# SS.net
KiCad netlist of a schematic drawn in EAGLE
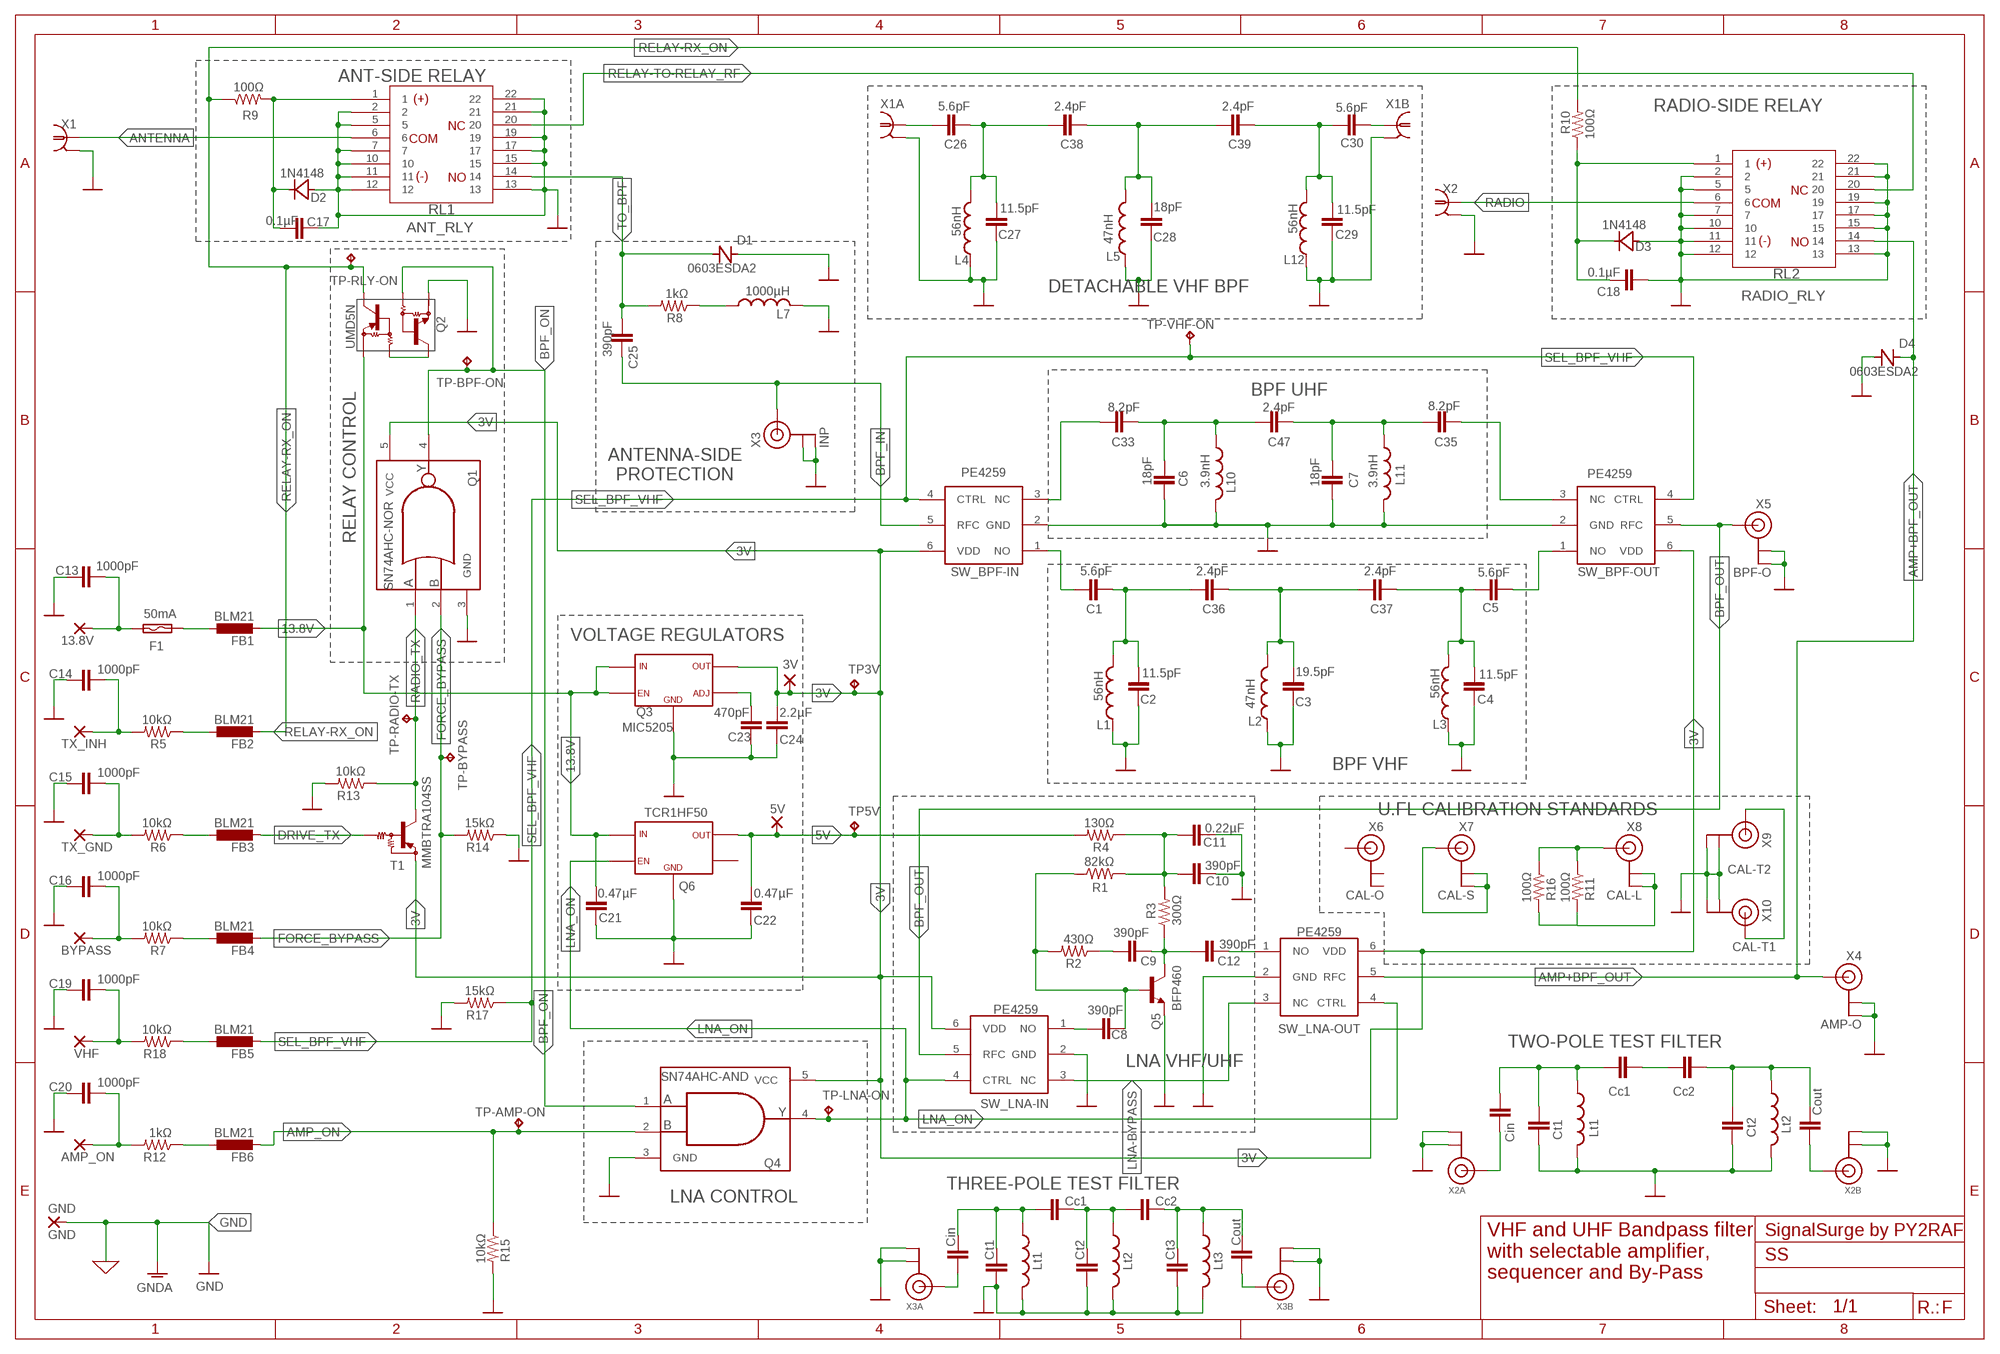
[diagram p0: schematic, sheet 1]

(export (version "E")
  (design (tool "Eeschema 10.0.6"))
  (components
    (comp (ref "3V")
      (value "3V")
      (footprint "eagle-import:JUMPER1")
      (libsource (lib "eagle-import") (part "JUMPER-1"))
    )
    (comp (ref "5V")
      (value "5V")
      (footprint "eagle-import:JUMPER1")
      (libsource (lib "eagle-import") (part "JUMPER-1"))
    )
    (comp (ref "13.8V")
      (value "13.8V")
      (footprint "eagle-import:JUMPER1")
      (fields (field (name "SPICEPREFIX") "X"))
      (libsource (lib "eagle-import") (part "JUMPER-1"))
    )
    (comp (ref "AMP_ON")
      (value "AMP_ON")
      (footprint "eagle-import:JUMPER1")
      (libsource (lib "eagle-import") (part "JUMPER-1"))
    )
    (comp (ref "BYPASS")
      (value "BYPASS")
      (footprint "eagle-import:JUMPER1")
      (libsource (lib "eagle-import") (part "JUMPER-1"))
    )
    (comp (ref "C1")
      (value "5.6pF")
      (footprint "eagle-import:0805")
      (libsource (lib "eagle-import") (part "C-0805"))
    )
    (comp (ref "C2")
      (value "11.5pF")
      (footprint "eagle-import:0805")
      (libsource (lib "eagle-import") (part "C-0805"))
    )
    (comp (ref "C3")
      (value "19.5pF")
      (footprint "eagle-import:0805")
      (libsource (lib "eagle-import") (part "C-0805"))
    )
    (comp (ref "C4")
      (value "11.5pF")
      (footprint "eagle-import:0805")
      (libsource (lib "eagle-import") (part "C-0805"))
    )
    (comp (ref "C5")
      (value "5.6pF")
      (footprint "eagle-import:0805")
      (libsource (lib "eagle-import") (part "C-0805"))
    )
    (comp (ref "C6")
      (value "18pF")
      (footprint "eagle-import:0805")
      (libsource (lib "eagle-import") (part "C-0805"))
    )
    (comp (ref "C7")
      (value "18pF")
      (footprint "eagle-import:0805")
      (libsource (lib "eagle-import") (part "C-0805"))
    )
    (comp (ref "C8")
      (value "390pF")
      (footprint "eagle-import:0805")
      (libsource (lib "eagle-import") (part "C-0805"))
    )
    (comp (ref "C9")
      (value "390pF")
      (footprint "eagle-import:0805")
      (libsource (lib "eagle-import") (part "C-0805"))
    )
    (comp (ref "C10")
      (value "390pF")
      (footprint "eagle-import:0805")
      (libsource (lib "eagle-import") (part "C-0805"))
    )
    (comp (ref "C11")
      (value "0.22µF")
      (footprint "eagle-import:0805")
      (libsource (lib "eagle-import") (part "C-0805"))
    )
    (comp (ref "C12")
      (value "390pF")
      (footprint "eagle-import:0805")
      (libsource (lib "eagle-import") (part "C-0805"))
    )
    (comp (ref "C13")
      (value "1000pF")
      (footprint "eagle-import:0805")
      (libsource (lib "eagle-import") (part "C-0805"))
    )
    (comp (ref "C14")
      (value "1000pF")
      (footprint "eagle-import:0805")
      (libsource (lib "eagle-import") (part "C-0805"))
    )
    (comp (ref "C15")
      (value "1000pF")
      (footprint "eagle-import:0805")
      (libsource (lib "eagle-import") (part "C-0805"))
    )
    (comp (ref "C16")
      (value "1000pF")
      (footprint "eagle-import:0805")
      (libsource (lib "eagle-import") (part "C-0805"))
    )
    (comp (ref "C17")
      (value "0.1µF")
      (footprint "eagle-import:0805")
      (libsource (lib "eagle-import") (part "C-0805"))
    )
    (comp (ref "C18")
      (value "0.1µF")
      (footprint "eagle-import:0805")
      (libsource (lib "eagle-import") (part "C-0805"))
    )
    (comp (ref "C19")
      (value "1000pF")
      (footprint "eagle-import:0805")
      (libsource (lib "eagle-import") (part "C-0805"))
    )
    (comp (ref "C20")
      (value "1000pF")
      (footprint "eagle-import:0805")
      (libsource (lib "eagle-import") (part "C-0805"))
    )
    (comp (ref "C21")
      (value "0.47µF")
      (footprint "eagle-import:0805")
      (libsource (lib "eagle-import") (part "C-0805"))
    )
    (comp (ref "C22")
      (value "0.47µF")
      (footprint "eagle-import:0805")
      (libsource (lib "eagle-import") (part "C-0805"))
    )
    (comp (ref "C23")
      (value "470pF")
      (footprint "eagle-import:0805")
      (libsource (lib "eagle-import") (part "C-0805"))
    )
    (comp (ref "C24")
      (value "2.2µF")
      (footprint "eagle-import:0805")
      (libsource (lib "eagle-import") (part "C-0805"))
    )
    (comp (ref "C25")
      (value "390pF")
      (footprint "eagle-import:0805")
      (libsource (lib "eagle-import") (part "C-0805"))
    )
    (comp (ref "C26")
      (value "5.6pF")
      (footprint "eagle-import:0805")
      (libsource (lib "eagle-import") (part "C-0805"))
    )
    (comp (ref "C27")
      (value "11.5pF")
      (footprint "eagle-import:0805")
      (libsource (lib "eagle-import") (part "C-0805"))
    )
    (comp (ref "C28")
      (value "18pF")
      (footprint "eagle-import:0805")
      (libsource (lib "eagle-import") (part "C-0805"))
    )
    (comp (ref "C29")
      (value "11.5pF")
      (footprint "eagle-import:0805")
      (libsource (lib "eagle-import") (part "C-0805"))
    )
    (comp (ref "C30")
      (value "5.6pF")
      (footprint "eagle-import:0805")
      (libsource (lib "eagle-import") (part "C-0805"))
    )
    (comp (ref "C31")
      (value "Ct1")
      (footprint "eagle-import:0805")
      (libsource (lib "eagle-import") (part "C-0805"))
    )
    (comp (ref "C32")
      (value "Ct2")
      (footprint "eagle-import:0805")
      (libsource (lib "eagle-import") (part "C-0805"))
    )
    (comp (ref "C33")
      (value "8.2pF")
      (footprint "eagle-import:0805")
      (libsource (lib "eagle-import") (part "C-0805"))
    )
    (comp (ref "C35")
      (value "8.2pF")
      (footprint "eagle-import:0805")
      (libsource (lib "eagle-import") (part "C-0805"))
    )
    (comp (ref "C36")
      (value "2.4pF")
      (footprint "eagle-import:0805")
      (libsource (lib "eagle-import") (part "C-0805"))
    )
    (comp (ref "C37")
      (value "2.4pF")
      (footprint "eagle-import:0805")
      (libsource (lib "eagle-import") (part "C-0805"))
    )
    (comp (ref "C38")
      (value "2.4pF")
      (footprint "eagle-import:0805")
      (libsource (lib "eagle-import") (part "C-0805"))
    )
    (comp (ref "C39")
      (value "2.4pF")
      (footprint "eagle-import:0805")
      (libsource (lib "eagle-import") (part "C-0805"))
    )
    (comp (ref "C40")
      (value "Cin")
      (footprint "eagle-import:0805")
      (libsource (lib "eagle-import") (part "C-0805"))
    )
    (comp (ref "C41")
      (value "Ct1")
      (footprint "eagle-import:0805")
      (libsource (lib "eagle-import") (part "C-0805"))
    )
    (comp (ref "C42")
      (value "Cc1")
      (footprint "eagle-import:0805")
      (libsource (lib "eagle-import") (part "C-0805"))
    )
    (comp (ref "C43")
      (value "Ct2")
      (footprint "eagle-import:0805")
      (libsource (lib "eagle-import") (part "C-0805"))
    )
    (comp (ref "C44")
      (value "Cc2")
      (footprint "eagle-import:0805")
      (libsource (lib "eagle-import") (part "C-0805"))
    )
    (comp (ref "C45")
      (value "Ct3")
      (footprint "eagle-import:0805")
      (libsource (lib "eagle-import") (part "C-0805"))
    )
    (comp (ref "C46")
      (value "Cout")
      (footprint "eagle-import:0805")
      (libsource (lib "eagle-import") (part "C-0805"))
    )
    (comp (ref "C47")
      (value "2.4pF")
      (footprint "eagle-import:0805")
      (libsource (lib "eagle-import") (part "C-0805"))
    )
    (comp (ref "D1")
      (value "0603ESDA2")
      (footprint "eagle-import:0603")
      (libsource (lib "eagle-import") (part "0603ESDA2"))
    )
    (comp (ref "D2")
      (value "1N4148")
      (footprint "eagle-import:SOD-323")
      (libsource (lib "eagle-import") (part "D-SOD323"))
    )
    (comp (ref "D3")
      (value "1N4148")
      (footprint "eagle-import:SOD-323")
      (libsource (lib "eagle-import") (part "D-SOD323"))
    )
    (comp (ref "D4")
      (value "0603ESDA2")
      (footprint "eagle-import:0603")
      (libsource (lib "eagle-import") (part "0603ESDA2"))
    )
    (comp (ref "F1")
      (value "50mA")
      (footprint "eagle-import:FUSE-1206")
      (fields (field (name "SPICEPREFIX") "B"))
      (libsource (lib "eagle-import") (part "FUSE-1206"))
    )
    (comp (ref "FB1")
      (value "BLM21")
      (footprint "eagle-import:0805")
      (libsource (lib "eagle-import") (part "FB-0805"))
    )
    (comp (ref "FB2")
      (value "BLM21")
      (footprint "eagle-import:0805")
      (libsource (lib "eagle-import") (part "FB-0805"))
    )
    (comp (ref "FB3")
      (value "BLM21")
      (footprint "eagle-import:0805")
      (libsource (lib "eagle-import") (part "FB-0805"))
    )
    (comp (ref "FB4")
      (value "BLM21")
      (footprint "eagle-import:0805")
      (libsource (lib "eagle-import") (part "FB-0805"))
    )
    (comp (ref "FB5")
      (value "BLM21")
      (footprint "eagle-import:0805")
      (libsource (lib "eagle-import") (part "FB-0805"))
    )
    (comp (ref "FB6")
      (value "BLM21")
      (footprint "eagle-import:0805")
      (libsource (lib "eagle-import") (part "FB-0805"))
    )
    (comp (ref "GND")
      (value "GND")
      (footprint "eagle-import:JUMPER1")
      (libsource (lib "eagle-import") (part "JUMPER-1"))
    )
    (comp (ref "L1")
      (value "56nH")
      (footprint "eagle-import:0805")
      (libsource (lib "eagle-import") (part "L-0805"))
    )
    (comp (ref "L2")
      (value "47nH")
      (footprint "eagle-import:0805")
      (libsource (lib "eagle-import") (part "L-0805"))
    )
    (comp (ref "L3")
      (value "56nH")
      (footprint "eagle-import:0805")
      (libsource (lib "eagle-import") (part "L-0805"))
    )
    (comp (ref "L4")
      (value "56nH")
      (footprint "eagle-import:0805")
      (libsource (lib "eagle-import") (part "L-0805"))
    )
    (comp (ref "L5")
      (value "47nH")
      (footprint "eagle-import:0805")
      (libsource (lib "eagle-import") (part "L-0805"))
    )
    (comp (ref "L6")
      (value "Lt1")
      (footprint "eagle-import:0805")
      (libsource (lib "eagle-import") (part "L-0805"))
    )
    (comp (ref "L7")
      (value "1000µH")
      (footprint "eagle-import:1207")
      (libsource (lib "eagle-import") (part "L-1207"))
    )
    (comp (ref "L8")
      (value "Lt2")
      (footprint "eagle-import:0805")
      (libsource (lib "eagle-import") (part "L-0805"))
    )
    (comp (ref "L9")
      (value "Lt3")
      (footprint "eagle-import:0805")
      (libsource (lib "eagle-import") (part "L-0805"))
    )
    (comp (ref "L10")
      (value "3.9nH")
      (footprint "eagle-import:0805")
      (libsource (lib "eagle-import") (part "L-0805"))
    )
    (comp (ref "L11")
      (value "3.9nH")
      (footprint "eagle-import:0805")
      (libsource (lib "eagle-import") (part "L-0805"))
    )
    (comp (ref "L12")
      (value "56nH")
      (footprint "eagle-import:0805")
      (libsource (lib "eagle-import") (part "L-0805"))
    )
    (comp (ref "L13")
      (value "Cc2")
      (footprint "eagle-import:0805")
      (libsource (lib "eagle-import") (part "C-0805"))
    )
    (comp (ref "L14")
      (value "Cout")
      (footprint "eagle-import:0805")
      (libsource (lib "eagle-import") (part "C-0805"))
    )
    (comp (ref "L15")
      (value "Cin")
      (footprint "eagle-import:0805")
      (libsource (lib "eagle-import") (part "C-0805"))
    )
    (comp (ref "L16")
      (value "Lt1")
      (footprint "eagle-import:0805")
      (libsource (lib "eagle-import") (part "L-0805"))
    )
    (comp (ref "L17")
      (value "Lt2")
      (footprint "eagle-import:0805")
      (libsource (lib "eagle-import") (part "L-0805"))
    )
    (comp (ref "L18")
      (value "Cc1")
      (footprint "eagle-import:0805")
      (libsource (lib "eagle-import") (part "C-0805"))
    )
    (comp (ref "Q1")
      (value "SN74AHC-NOR")
      (footprint "eagle-import:SC70-5")
      (libsource (lib "eagle-import") (part "SN74AHC-NOR"))
    )
    (comp (ref "Q2")
      (value "UMD5N")
      (footprint "eagle-import:SOT363")
      (libsource (lib "eagle-import") (part "UMD5N"))
    )
    (comp (ref "Q3")
      (value "MIC5205")
      (footprint "eagle-import:SOT23-5")
      (libsource (lib "eagle-import") (part "MIC5205"))
    )
    (comp (ref "Q4")
      (value "SN74AHC-AND")
      (footprint "eagle-import:SC70-5")
      (libsource (lib "eagle-import") (part "SN74AHC-AND"))
    )
    (comp (ref "Q5")
      (value "BFP460")
      (footprint "eagle-import:SOT343R")
      (libsource (lib "eagle-import") (part "BFP460"))
    )
    (comp (ref "Q6")
      (value "TCR1HF50")
      (footprint "eagle-import:SC-74A")
      (libsource (lib "eagle-import") (part "TCR1HF"))
    )
    (comp (ref "R1")
      (value "82kΩ")
      (footprint "eagle-import:1206")
      (libsource (lib "eagle-import") (part "R-1206"))
    )
    (comp (ref "R2")
      (value "430Ω")
      (footprint "eagle-import:1206")
      (libsource (lib "eagle-import") (part "R-1206"))
    )
    (comp (ref "R3")
      (value "300Ω")
      (footprint "eagle-import:1206")
      (libsource (lib "eagle-import") (part "R-1206"))
    )
    (comp (ref "R4")
      (value "130Ω")
      (footprint "eagle-import:1206")
      (libsource (lib "eagle-import") (part "R-1206"))
    )
    (comp (ref "R5")
      (value "10kΩ")
      (footprint "eagle-import:1206")
      (libsource (lib "eagle-import") (part "R-1206"))
    )
    (comp (ref "R6")
      (value "10kΩ")
      (footprint "eagle-import:1206")
      (libsource (lib "eagle-import") (part "R-1206"))
    )
    (comp (ref "R7")
      (value "10kΩ")
      (footprint "eagle-import:1206")
      (libsource (lib "eagle-import") (part "R-1206"))
    )
    (comp (ref "R8")
      (value "1kΩ")
      (footprint "eagle-import:1206")
      (libsource (lib "eagle-import") (part "R-1206"))
    )
    (comp (ref "R9")
      (value "100Ω")
      (footprint "eagle-import:1206")
      (libsource (lib "eagle-import") (part "R-1206"))
    )
    (comp (ref "R10")
      (value "100Ω")
      (footprint "eagle-import:1206")
      (libsource (lib "eagle-import") (part "R-1206"))
    )
    (comp (ref "R11")
      (value "100Ω")
      (footprint "eagle-import:1206")
      (libsource (lib "eagle-import") (part "R-1206"))
    )
    (comp (ref "R12")
      (value "1kΩ")
      (footprint "eagle-import:1206")
      (libsource (lib "eagle-import") (part "R-1206"))
    )
    (comp (ref "R13")
      (value "10kΩ")
      (footprint "eagle-import:1206")
      (libsource (lib "eagle-import") (part "R-1206"))
    )
    (comp (ref "R14")
      (value "15kΩ")
      (footprint "eagle-import:1206")
      (libsource (lib "eagle-import") (part "R-1206"))
    )
    (comp (ref "R15")
      (value "10kΩ")
      (footprint "eagle-import:1206")
      (libsource (lib "eagle-import") (part "R-1206"))
    )
    (comp (ref "R16")
      (value "100Ω")
      (footprint "eagle-import:1206")
      (libsource (lib "eagle-import") (part "R-1206"))
    )
    (comp (ref "R17")
      (value "15kΩ")
      (footprint "eagle-import:1206")
      (libsource (lib "eagle-import") (part "R-1206"))
    )
    (comp (ref "R18")
      (value "10kΩ")
      (footprint "eagle-import:1206")
      (libsource (lib "eagle-import") (part "R-1206"))
    )
    (comp (ref "RL1")
      (value "ANT_RLY")
      (footprint "eagle-import:RELAY-TE-HF3")
      (libsource (lib "eagle-import") (part "RELAY-TE-HF3"))
    )
    (comp (ref "RL2")
      (value "RADIO_RLY")
      (footprint "eagle-import:RELAY-TE-HF3")
      (libsource (lib "eagle-import") (part "RELAY-TE-HF3"))
    )
    (comp (ref "SW_BPF-IN")
      (value "PE4259")
      (footprint "eagle-import:SC-70")
      (libsource (lib "eagle-import") (part "PE4259"))
    )
    (comp (ref "SW_BPF-OUT")
      (value "PE4259")
      (footprint "eagle-import:SC-70")
      (libsource (lib "eagle-import") (part "PE4259"))
    )
    (comp (ref "SW_LNA-IN")
      (value "PE4259")
      (footprint "eagle-import:SC-70")
      (libsource (lib "eagle-import") (part "PE4259"))
    )
    (comp (ref "SW_LNA-OUT")
      (value "PE4259")
      (footprint "eagle-import:SC-70")
      (libsource (lib "eagle-import") (part "PE4259"))
    )
    (comp (ref "T1")
      (value "MMBTRA104SS")
      (footprint "eagle-import:SC59-BEC")
      (libsource (lib "eagle-import") (part "-PNP_DRIVER-SC59-BECMUN2111T1"))
    )
    (comp (ref "TP-AMP-ON")
      (value "TPB1,27")
      (footprint "eagle-import:B1,27")
      (libsource (lib "eagle-import") (part "TPB1,27"))
    )
    (comp (ref "TP-BPF-ON")
      (value "TPB1,27")
      (footprint "eagle-import:B1,27")
      (libsource (lib "eagle-import") (part "TPB1,27"))
    )
    (comp (ref "TP-BYPASS")
      (value "TPB1,27")
      (footprint "eagle-import:B1,27")
      (libsource (lib "eagle-import") (part "TPB1,27"))
    )
    (comp (ref "TP-LNA-ON")
      (value "TPB1,27")
      (footprint "eagle-import:B1,27")
      (libsource (lib "eagle-import") (part "TPB1,27"))
    )
    (comp (ref "TP-RADIO-TX")
      (value "TPB1,27")
      (footprint "eagle-import:B1,27")
      (libsource (lib "eagle-import") (part "TPB1,27"))
    )
    (comp (ref "TP-RLY-ON")
      (value "TPB1,27")
      (footprint "eagle-import:B1,27")
      (libsource (lib "eagle-import") (part "TPB1,27"))
    )
    (comp (ref "TP-VHF-ON")
      (value "TPB1,27")
      (footprint "eagle-import:B1,27")
      (libsource (lib "eagle-import") (part "TPB1,27"))
    )
    (comp (ref "TP3V")
      (value "TPB1,27")
      (footprint "eagle-import:B1,27")
      (libsource (lib "eagle-import") (part "TPB1,27"))
    )
    (comp (ref "TP5V")
      (value "TPB1,27")
      (footprint "eagle-import:B1,27")
      (libsource (lib "eagle-import") (part "TPB1,27"))
    )
    (comp (ref "TX_GND")
      (value "TX_GND")
      (footprint "eagle-import:JUMPER1")
      (libsource (lib "eagle-import") (part "JUMPER-1"))
    )
    (comp (ref "TX_INH")
      (value "TX INH")
      (footprint "eagle-import:JUMPER1")
      (fields (field (name "SPICEPREFIX") "X"))
      (libsource (lib "eagle-import") (part "JUMPER-1"))
    )
    (comp (ref "VHF")
      (value "VHF")
      (footprint "eagle-import:JUMPER1")
      (libsource (lib "eagle-import") (part "JUMPER-1"))
    )
    (comp (ref "X1")
      (value "ANTENNA")
      (footprint "eagle-import:SMA-RF")
      (libsource (lib "eagle-import") (part "SMA-PCB"))
    )
    (comp (ref "X1A")
      (value "SMA-EDGE")
      (footprint "eagle-import:SMA-EDGE")
      (libsource (lib "eagle-import") (part "SMA-EDGE"))
    )
    (comp (ref "X1B")
      (value "SMA-EDGE")
      (footprint "eagle-import:SMA-EDGE")
      (libsource (lib "eagle-import") (part "SMA-EDGE"))
    )
    (comp (ref "X2")
      (value "RADIO")
      (footprint "eagle-import:SMA-RF")
      (libsource (lib "eagle-import") (part "SMA-PCB"))
    )
    (comp (ref "X2A")
      (value "ANTENNA_U.FL")
      (footprint "eagle-import:U.FL")
      (libsource (lib "eagle-import") (part "ANTENNA_U.FL"))
    )
    (comp (ref "X2B")
      (value "ANTENNA_U.FL")
      (footprint "eagle-import:U.FL")
      (libsource (lib "eagle-import") (part "ANTENNA_U.FL"))
    )
    (comp (ref "X3")
      (value "INP")
      (footprint "eagle-import:U.FL")
      (libsource (lib "eagle-import") (part "ANTENNA_U.FL"))
    )
    (comp (ref "X3A")
      (value "ANTENNA_U.FL")
      (footprint "eagle-import:U.FL")
      (libsource (lib "eagle-import") (part "ANTENNA_U.FL"))
    )
    (comp (ref "X3B")
      (value "ANTENNA_U.FL")
      (footprint "eagle-import:U.FL")
      (libsource (lib "eagle-import") (part "ANTENNA_U.FL"))
    )
    (comp (ref "X4")
      (value "AMP-O")
      (footprint "eagle-import:U.FL")
      (libsource (lib "eagle-import") (part "ANTENNA_U.FL"))
    )
    (comp (ref "X5")
      (value "BPF-O")
      (footprint "eagle-import:U.FL")
      (libsource (lib "eagle-import") (part "ANTENNA_U.FL"))
    )
    (comp (ref "X6")
      (value "CAL-O")
      (footprint "eagle-import:U.FL")
      (libsource (lib "eagle-import") (part "ANTENNA_U.FL"))
    )
    (comp (ref "X7")
      (value "CAL-S")
      (footprint "eagle-import:U.FL")
      (libsource (lib "eagle-import") (part "ANTENNA_U.FL"))
    )
    (comp (ref "X8")
      (value "CAL-L")
      (footprint "eagle-import:U.FL")
      (libsource (lib "eagle-import") (part "ANTENNA_U.FL"))
    )
    (comp (ref "X9")
      (value "CAL-T2")
      (footprint "eagle-import:U.FL")
      (libsource (lib "eagle-import") (part "ANTENNA_U.FL"))
    )
    (comp (ref "X10")
      (value "CAL-T1")
      (footprint "eagle-import:U.FL")
      (libsource (lib "eagle-import") (part "ANTENNA_U.FL"))
    )
  )
  (nets
    (net (code "1") (name "3V") (class "Default")
      (node (ref "3V") (pin "1") (pinfunction "P_1") (pintype "passive"))
      (node (ref "C24") (pin "P$2") (pinfunction "2_P$2") (pintype "passive"))
      (node (ref "Q1") (pin "5") (pinfunction "VCC_5") (pintype "bidirectional"))
      (node (ref "Q3") (pin "5") (pinfunction "VOUT_5") (pintype "power_in"))
      (node (ref "Q4") (pin "5") (pinfunction "VCC_5") (pintype "bidirectional"))
      (node (ref "SW_BPF-IN") (pin "6") (pinfunction "VDD_6") (pintype "power_in"))
      (node (ref "SW_BPF-OUT") (pin "6") (pinfunction "VDD_6") (pintype "power_in"))
      (node (ref "SW_LNA-IN") (pin "6") (pinfunction "VDD_6") (pintype "power_in"))
      (node (ref "SW_LNA-OUT") (pin "6") (pinfunction "VDD_6") (pintype "power_in"))
      (node (ref "T1") (pin "E") (pinfunction "E_E") (pintype "passive"))
      (node (ref "TP3V") (pin "TP") (pinfunction "TP_TP") (pintype "input"))
    )
    (net (code "2") (name "5V") (class "Default")
      (node (ref "5V") (pin "1") (pinfunction "P_1") (pintype "passive"))
      (node (ref "C22") (pin "P$2") (pinfunction "2_P$2") (pintype "passive"))
      (node (ref "Q6") (pin "5") (pinfunction "VOUT_5") (pintype "power_in"))
      (node (ref "R4") (pin "2") (pinfunction "2_2") (pintype "passive"))
      (node (ref "TP5V") (pin "TP") (pinfunction "TP_TP") (pintype "input"))
    )
    (net (code "3") (name "13.8V") (class "Default")
      (node (ref "C21") (pin "P$2") (pinfunction "2_P$2") (pintype "passive"))
      (node (ref "FB1") (pin "P$2") (pinfunction "2_P$2") (pintype "passive"))
      (node (ref "Q2") (pin "4") (pinfunction "6_4") (pintype "passive"))
      (node (ref "Q3") (pin "1") (pinfunction "VIN_1") (pintype "power_in"))
      (node (ref "Q3") (pin "3") (pinfunction "EN_3") (pintype "input"))
      (node (ref "Q6") (pin "1") (pinfunction "VIN_1") (pintype "power_in"))
    )
    (net (code "4") (name "AMP+BPF_OUT") (class "Default")
      (node (ref "D4") (pin "1") (pinfunction "A_1") (pintype "passive"))
      (node (ref "RL2") (pin "14") (pinfunction "14_14") (pintype "bidirectional"))
      (node (ref "SW_LNA-OUT") (pin "5") (pinfunction "RFC_5") (pintype "bidirectional"))
      (node (ref "X4") (pin "3") (pinfunction "SIGNAL_3") (pintype "passive"))
    )
    (net (code "5") (name "AMP_ON") (class "Default")
      (node (ref "FB6") (pin "P$2") (pinfunction "2_P$2") (pintype "passive"))
      (node (ref "Q4") (pin "2") (pinfunction "B_2") (pintype "input"))
      (node (ref "R15") (pin "1") (pinfunction "1_1") (pintype "passive"))
      (node (ref "TP-AMP-ON") (pin "TP") (pinfunction "TP_TP") (pintype "input"))
    )
    (net (code "6") (name "ANTENNA") (class "Default")
      (node (ref "RL1") (pin "6") (pinfunction "6_6") (pintype "bidirectional"))
      (node (ref "X1") (pin "1") (pinfunction "1_1") (pintype "passive"))
    )
    (net (code "7") (name "BPF_IN") (class "Default")
      (node (ref "C25") (pin "P$1") (pinfunction "1_P$1") (pintype "passive"))
      (node (ref "SW_BPF-IN") (pin "5") (pinfunction "RFC_5") (pintype "bidirectional"))
      (node (ref "X3") (pin "3") (pinfunction "SIGNAL_3") (pintype "passive"))
    )
    (net (code "8") (name "BPF_ON") (class "Default")
      (node (ref "Q1") (pin "4") (pinfunction "Y_4") (pintype "output"))
      (node (ref "Q2") (pin "2") (pinfunction "2_2") (pintype "passive"))
      (node (ref "Q4") (pin "1") (pinfunction "A_1") (pintype "input"))
      (node (ref "TP-BPF-ON") (pin "TP") (pinfunction "TP_TP") (pintype "input"))
    )
    (net (code "9") (name "BPF_OUT") (class "Default")
      (node (ref "SW_BPF-OUT") (pin "5") (pinfunction "RFC_5") (pintype "bidirectional"))
      (node (ref "SW_LNA-IN") (pin "5") (pinfunction "RFC_5") (pintype "bidirectional"))
      (node (ref "X5") (pin "3") (pinfunction "SIGNAL_3") (pintype "passive"))
    )
    (net (code "10") (name "DRIVE_TX") (class "Default")
      (node (ref "FB3") (pin "P$2") (pinfunction "2_P$2") (pintype "passive"))
      (node (ref "T1") (pin "B") (pinfunction "B_B") (pintype "passive"))
    )
    (net (code "11") (name "FORCE_BYPASS") (class "Default")
      (node (ref "FB4") (pin "P$2") (pinfunction "2_P$2") (pintype "passive"))
      (node (ref "Q1") (pin "2") (pinfunction "B_2") (pintype "input"))
      (node (ref "R14") (pin "2") (pinfunction "2_2") (pintype "passive"))
      (node (ref "TP-BYPASS") (pin "TP") (pinfunction "TP_TP") (pintype "input"))
    )
    (net (code "12") (name "GND") (class "Default")
      (node (ref "C10") (pin "P$2") (pinfunction "2_P$2") (pintype "passive"))
      (node (ref "C11") (pin "P$2") (pinfunction "2_P$2") (pintype "passive"))
      (node (ref "C13") (pin "P$1") (pinfunction "1_P$1") (pintype "passive"))
      (node (ref "C14") (pin "P$1") (pinfunction "1_P$1") (pintype "passive"))
      (node (ref "C15") (pin "P$1") (pinfunction "1_P$1") (pintype "passive"))
      (node (ref "C16") (pin "P$1") (pinfunction "1_P$1") (pintype "passive"))
      (node (ref "C17") (pin "P$1") (pinfunction "1_P$1") (pintype "passive"))
      (node (ref "C18") (pin "P$2") (pinfunction "2_P$2") (pintype "passive"))
      (node (ref "C19") (pin "P$1") (pinfunction "1_P$1") (pintype "passive"))
      (node (ref "C2") (pin "P$2") (pinfunction "2_P$2") (pintype "passive"))
      (node (ref "C20") (pin "P$1") (pinfunction "1_P$1") (pintype "passive"))
      (node (ref "C21") (pin "P$1") (pinfunction "1_P$1") (pintype "passive"))
      (node (ref "C22") (pin "P$1") (pinfunction "1_P$1") (pintype "passive"))
      (node (ref "C23") (pin "P$1") (pinfunction "1_P$1") (pintype "passive"))
      (node (ref "C24") (pin "P$1") (pinfunction "1_P$1") (pintype "passive"))
      (node (ref "C27") (pin "P$2") (pinfunction "2_P$2") (pintype "passive"))
      (node (ref "C28") (pin "P$2") (pinfunction "2_P$2") (pintype "passive"))
      (node (ref "C29") (pin "P$2") (pinfunction "2_P$2") (pintype "passive"))
      (node (ref "C3") (pin "P$2") (pinfunction "2_P$2") (pintype "passive"))
      (node (ref "C31") (pin "P$1") (pinfunction "1_P$1") (pintype "passive"))
      (node (ref "C32") (pin "P$1") (pinfunction "1_P$1") (pintype "passive"))
      (node (ref "C4") (pin "P$2") (pinfunction "2_P$2") (pintype "passive"))
      (node (ref "C41") (pin "P$2") (pinfunction "2_P$2") (pintype "passive"))
      (node (ref "C43") (pin "P$2") (pinfunction "2_P$2") (pintype "passive"))
      (node (ref "C45") (pin "P$2") (pinfunction "2_P$2") (pintype "passive"))
      (node (ref "C6") (pin "P$1") (pinfunction "1_P$1") (pintype "passive"))
      (node (ref "C7") (pin "P$1") (pinfunction "1_P$1") (pintype "passive"))
      (node (ref "D1") (pin "1") (pinfunction "A_1") (pintype "passive"))
      (node (ref "D2") (pin "A") (pinfunction "A_A") (pintype "passive"))
      (node (ref "D3") (pin "A") (pinfunction "A_A") (pintype "passive"))
      (node (ref "D4") (pin "2") (pinfunction "C_2") (pintype "passive"))
      (node (ref "GND") (pin "1") (pinfunction "P_1") (pintype "passive"))
      (node (ref "L1") (pin "P$1") (pinfunction "1_P$1") (pintype "passive"))
      (node (ref "L10") (pin "P$2") (pinfunction "2_P$2") (pintype "passive"))
      (node (ref "L11") (pin "P$2") (pinfunction "2_P$2") (pintype "passive"))
      (node (ref "L12") (pin "P$2") (pinfunction "2_P$2") (pintype "passive"))
      (node (ref "L16") (pin "P$2") (pinfunction "2_P$2") (pintype "passive"))
      (node (ref "L17") (pin "P$2") (pinfunction "2_P$2") (pintype "passive"))
      (node (ref "L2") (pin "P$1") (pinfunction "1_P$1") (pintype "passive"))
      (node (ref "L3") (pin "P$2") (pinfunction "2_P$2") (pintype "passive"))
      (node (ref "L4") (pin "P$1") (pinfunction "1_P$1") (pintype "passive"))
      (node (ref "L5") (pin "P$1") (pinfunction "1_P$1") (pintype "passive"))
      (node (ref "L6") (pin "P$2") (pinfunction "2_P$2") (pintype "passive"))
      (node (ref "L7") (pin "P$2") (pinfunction "2_P$2") (pintype "passive"))
      (node (ref "L8") (pin "P$2") (pinfunction "2_P$2") (pintype "passive"))
      (node (ref "L9") (pin "P$2") (pinfunction "2_P$2") (pintype "passive"))
      (node (ref "Q1") (pin "3") (pinfunction "GND_3") (pintype "bidirectional"))
      (node (ref "Q2") (pin "1") (pinfunction "1_1") (pintype "passive"))
      (node (ref "Q3") (pin "2") (pinfunction "GND_2") (pintype "power_in"))
      (node (ref "Q4") (pin "3") (pinfunction "GND_3") (pintype "bidirectional"))
      (node (ref "Q5") (pin "1") (pinfunction "E_1") (pintype "passive"))
      (node (ref "Q5") (pin "3") (pinfunction "E_3") (pintype "passive"))
      (node (ref "Q6") (pin "2") (pinfunction "GND_2") (pintype "power_in"))
      (node (ref "R13") (pin "2") (pinfunction "2_2") (pintype "passive"))
      (node (ref "R14") (pin "1") (pinfunction "1_1") (pintype "passive"))
      (node (ref "R15") (pin "2") (pinfunction "2_2") (pintype "passive"))
      (node (ref "R17") (pin "2") (pinfunction "2_2") (pintype "passive"))
      (node (ref "RL1") (pin "10") (pinfunction "10_10") (pintype "power_in"))
      (node (ref "RL1") (pin "11") (pinfunction "11_11") (pintype "power_in"))
      (node (ref "RL1") (pin "12") (pinfunction "12_12") (pintype "power_in"))
      (node (ref "RL1") (pin "13") (pinfunction "13_13") (pintype "power_in"))
      (node (ref "RL1") (pin "15") (pinfunction "15_15") (pintype "power_in"))
      (node (ref "RL1") (pin "17") (pinfunction "17_17") (pintype "power_in"))
      (node (ref "RL1") (pin "19") (pinfunction "19_19") (pintype "power_in"))
      (node (ref "RL1") (pin "2") (pinfunction "2_2") (pintype "power_in"))
      (node (ref "RL1") (pin "21") (pinfunction "21_21") (pintype "power_in"))
      (node (ref "RL1") (pin "22") (pinfunction "22_22") (pintype "power_in"))
      (node (ref "RL1") (pin "5") (pinfunction "5_5") (pintype "power_in"))
      (node (ref "RL1") (pin "7") (pinfunction "7_7") (pintype "power_in"))
      (node (ref "RL2") (pin "10") (pinfunction "10_10") (pintype "power_in"))
      (node (ref "RL2") (pin "11") (pinfunction "11_11") (pintype "power_in"))
      (node (ref "RL2") (pin "12") (pinfunction "12_12") (pintype "power_in"))
      (node (ref "RL2") (pin "13") (pinfunction "13_13") (pintype "power_in"))
      (node (ref "RL2") (pin "15") (pinfunction "15_15") (pintype "power_in"))
      (node (ref "RL2") (pin "17") (pinfunction "17_17") (pintype "power_in"))
      (node (ref "RL2") (pin "19") (pinfunction "19_19") (pintype "power_in"))
      (node (ref "RL2") (pin "2") (pinfunction "2_2") (pintype "power_in"))
      (node (ref "RL2") (pin "21") (pinfunction "21_21") (pintype "power_in"))
      (node (ref "RL2") (pin "22") (pinfunction "22_22") (pintype "power_in"))
      (node (ref "RL2") (pin "5") (pinfunction "5_5") (pintype "power_in"))
      (node (ref "RL2") (pin "7") (pinfunction "7_7") (pintype "power_in"))
      (node (ref "SW_BPF-IN") (pin "2") (pinfunction "GND_2") (pintype "bidirectional"))
      (node (ref "SW_BPF-OUT") (pin "2") (pinfunction "GND_2") (pintype "bidirectional"))
      (node (ref "SW_LNA-IN") (pin "2") (pinfunction "GND_2") (pintype "bidirectional"))
      (node (ref "SW_LNA-OUT") (pin "2") (pinfunction "GND_2") (pintype "bidirectional"))
      (node (ref "X1") (pin "2") (pinfunction "2_2") (pintype "passive"))
      (node (ref "X1") (pin "3") (pinfunction "2_3") (pintype "passive"))
      (node (ref "X1") (pin "4") (pinfunction "2_4") (pintype "passive"))
      (node (ref "X1") (pin "5") (pinfunction "2_5") (pintype "passive"))
      (node (ref "X10") (pin "1") (pinfunction "GND_1") (pintype "passive"))
      (node (ref "X10") (pin "2") (pinfunction "GND_2") (pintype "passive"))
      (node (ref "X1A") (pin "P$1") (pinfunction "2_P$1") (pintype "passive"))
      (node (ref "X1A") (pin "P$2") (pinfunction "2_P$2") (pintype "passive"))
      (node (ref "X1A") (pin "P$4") (pinfunction "2_P$4") (pintype "passive"))
      (node (ref "X1A") (pin "P$5") (pinfunction "2_P$5") (pintype "passive"))
      (node (ref "X1A") (pin "P$6") (pinfunction "2_P$6") (pintype "passive"))
      (node (ref "X1A") (pin "P$7") (pinfunction "2_P$7") (pintype "passive"))
      (node (ref "X1B") (pin "P$1") (pinfunction "2_P$1") (pintype "passive"))
      (node (ref "X1B") (pin "P$2") (pinfunction "2_P$2") (pintype "passive"))
      (node (ref "X1B") (pin "P$4") (pinfunction "2_P$4") (pintype "passive"))
      (node (ref "X1B") (pin "P$5") (pinfunction "2_P$5") (pintype "passive"))
      (node (ref "X1B") (pin "P$6") (pinfunction "2_P$6") (pintype "passive"))
      (node (ref "X1B") (pin "P$7") (pinfunction "2_P$7") (pintype "passive"))
      (node (ref "X2") (pin "2") (pinfunction "2_2") (pintype "passive"))
      (node (ref "X2") (pin "3") (pinfunction "2_3") (pintype "passive"))
      (node (ref "X2") (pin "4") (pinfunction "2_4") (pintype "passive"))
      (node (ref "X2") (pin "5") (pinfunction "2_5") (pintype "passive"))
      (node (ref "X2A") (pin "1") (pinfunction "GND_1") (pintype "passive"))
      (node (ref "X2A") (pin "2") (pinfunction "GND_2") (pintype "passive"))
      (node (ref "X2B") (pin "1") (pinfunction "GND_1") (pintype "passive"))
      (node (ref "X2B") (pin "2") (pinfunction "GND_2") (pintype "passive"))
      (node (ref "X3") (pin "1") (pinfunction "GND_1") (pintype "passive"))
      (node (ref "X3") (pin "2") (pinfunction "GND_2") (pintype "passive"))
      (node (ref "X3A") (pin "1") (pinfunction "GND_1") (pintype "passive"))
      (node (ref "X3A") (pin "2") (pinfunction "GND_2") (pintype "passive"))
      (node (ref "X3B") (pin "1") (pinfunction "GND_1") (pintype "passive"))
      (node (ref "X3B") (pin "2") (pinfunction "GND_2") (pintype "passive"))
      (node (ref "X4") (pin "1") (pinfunction "GND_1") (pintype "passive"))
      (node (ref "X4") (pin "2") (pinfunction "GND_2") (pintype "passive"))
      (node (ref "X5") (pin "1") (pinfunction "GND_1") (pintype "passive"))
      (node (ref "X5") (pin "2") (pinfunction "GND_2") (pintype "passive"))
      (node (ref "X9") (pin "1") (pinfunction "GND_1") (pintype "passive"))
      (node (ref "X9") (pin "2") (pinfunction "GND_2") (pintype "passive"))
    )
    (net (code "13") (name "LNA-BYPASS") (class "Default")
      (node (ref "SW_LNA-IN") (pin "3") (pinfunction "NC_3") (pintype "bidirectional"))
      (node (ref "SW_LNA-OUT") (pin "3") (pinfunction "NC_3") (pintype "bidirectional"))
    )
    (net (code "14") (name "LNA_ON") (class "Default")
      (node (ref "Q4") (pin "4") (pinfunction "Y_4") (pintype "output"))
      (node (ref "Q6") (pin "3") (pinfunction "EN_3") (pintype "input"))
      (node (ref "SW_LNA-IN") (pin "4") (pinfunction "CTRL_4") (pintype "input"))
      (node (ref "SW_LNA-OUT") (pin "4") (pinfunction "CTRL_4") (pintype "input"))
      (node (ref "TP-LNA-ON") (pin "TP") (pinfunction "TP_TP") (pintype "input"))
    )
    (net (code "15") (name "Net-(13.8V-P)") (class "Default")
      (node (ref "13.8V") (pin "1") (pinfunction "P_1") (pintype "passive"))
      (node (ref "C13") (pin "P$2") (pinfunction "2_P$2") (pintype "passive"))
      (node (ref "F1") (pin "2") (pinfunction "2_2") (pintype "passive"))
    )
    (net (code "16") (name "Net-(AMP_ON-P)") (class "Default")
      (node (ref "AMP_ON") (pin "1") (pinfunction "P_1") (pintype "passive"))
      (node (ref "C20") (pin "P$2") (pinfunction "2_P$2") (pintype "passive"))
      (node (ref "R12") (pin "2") (pinfunction "2_2") (pintype "passive"))
    )
    (net (code "17") (name "Net-(BYPASS-P)") (class "Default")
      (node (ref "BYPASS") (pin "1") (pinfunction "P_1") (pintype "passive"))
      (node (ref "C16") (pin "P$2") (pinfunction "2_P$2") (pintype "passive"))
      (node (ref "R7") (pin "2") (pinfunction "2_2") (pintype "passive"))
    )
    (net (code "18") (name "Net-(C1-1)") (class "Default")
      (node (ref "C1") (pin "P$1") (pinfunction "1_P$1") (pintype "passive"))
      (node (ref "C2") (pin "P$1") (pinfunction "1_P$1") (pintype "passive"))
      (node (ref "C36") (pin "P$2") (pinfunction "2_P$2") (pintype "passive"))
      (node (ref "L1") (pin "P$2") (pinfunction "2_P$2") (pintype "passive"))
    )
    (net (code "19") (name "Net-(C1-2)") (class "Default")
      (node (ref "C1") (pin "P$2") (pinfunction "2_P$2") (pintype "passive"))
      (node (ref "SW_BPF-IN") (pin "1") (pinfunction "NO_1") (pintype "bidirectional"))
    )
    (net (code "20") (name "Net-(C3-1)") (class "Default")
      (node (ref "C3") (pin "P$1") (pinfunction "1_P$1") (pintype "passive"))
      (node (ref "C36") (pin "P$1") (pinfunction "1_P$1") (pintype "passive"))
      (node (ref "C37") (pin "P$2") (pinfunction "2_P$2") (pintype "passive"))
      (node (ref "L2") (pin "P$2") (pinfunction "2_P$2") (pintype "passive"))
    )
    (net (code "21") (name "Net-(C5-2)") (class "Default")
      (node (ref "C5") (pin "P$2") (pinfunction "2_P$2") (pintype "passive"))
      (node (ref "SW_BPF-OUT") (pin "1") (pinfunction "NO_1") (pintype "bidirectional"))
    )
    (net (code "22") (name "Net-(C8-1)") (class "Default")
      (node (ref "C8") (pin "P$1") (pinfunction "1_P$1") (pintype "passive"))
      (node (ref "SW_LNA-IN") (pin "1") (pinfunction "NO_1") (pintype "bidirectional"))
    )
    (net (code "23") (name "Net-(C8-2)") (class "Default")
      (node (ref "C8") (pin "P$2") (pinfunction "2_P$2") (pintype "passive"))
      (node (ref "Q5") (pin "4") (pinfunction "B_4") (pintype "passive"))
      (node (ref "R1") (pin "1") (pinfunction "1_1") (pintype "passive"))
      (node (ref "R2") (pin "2") (pinfunction "2_2") (pintype "passive"))
    )
    (net (code "24") (name "Net-(C9-1)") (class "Default")
      (node (ref "C9") (pin "P$1") (pinfunction "1_P$1") (pintype "passive"))
      (node (ref "R2") (pin "1") (pinfunction "1_1") (pintype "passive"))
    )
    (net (code "25") (name "Net-(C10-1)") (class "Default")
      (node (ref "C10") (pin "P$1") (pinfunction "1_P$1") (pintype "passive"))
      (node (ref "C11") (pin "P$1") (pinfunction "1_P$1") (pintype "passive"))
      (node (ref "R1") (pin "2") (pinfunction "2_2") (pintype "passive"))
      (node (ref "R3") (pin "2") (pinfunction "2_2") (pintype "passive"))
      (node (ref "R4") (pin "1") (pinfunction "1_1") (pintype "passive"))
    )
    (net (code "26") (name "Net-(C12-1)") (class "Default")
      (node (ref "C12") (pin "P$1") (pinfunction "1_P$1") (pintype "passive"))
      (node (ref "C9") (pin "P$2") (pinfunction "2_P$2") (pintype "passive"))
      (node (ref "Q5") (pin "2") (pinfunction "C_2") (pintype "passive"))
      (node (ref "R3") (pin "1") (pinfunction "1_1") (pintype "passive"))
    )
    (net (code "27") (name "Net-(C12-2)") (class "Default")
      (node (ref "C12") (pin "P$2") (pinfunction "2_P$2") (pintype "passive"))
      (node (ref "SW_LNA-OUT") (pin "1") (pinfunction "NO_1") (pintype "bidirectional"))
    )
    (net (code "28") (name "Net-(C14-2)") (class "Default")
      (node (ref "C14") (pin "P$2") (pinfunction "2_P$2") (pintype "passive"))
      (node (ref "R5") (pin "2") (pinfunction "2_2") (pintype "passive"))
      (node (ref "TX_INH") (pin "1") (pinfunction "P_1") (pintype "passive"))
    )
    (net (code "29") (name "Net-(C15-2)") (class "Default")
      (node (ref "C15") (pin "P$2") (pinfunction "2_P$2") (pintype "passive"))
      (node (ref "R6") (pin "2") (pinfunction "2_2") (pintype "passive"))
      (node (ref "TX_GND") (pin "1") (pinfunction "P_1") (pintype "passive"))
    )
    (net (code "30") (name "Net-(C17-2)") (class "Default")
      (node (ref "C17") (pin "P$2") (pinfunction "2_P$2") (pintype "passive"))
      (node (ref "D2") (pin "C") (pinfunction "C_C") (pintype "passive"))
      (node (ref "R9") (pin "2") (pinfunction "2_2") (pintype "passive"))
      (node (ref "RL1") (pin "1") (pinfunction "1_1") (pintype "power_in"))
    )
    (net (code "31") (name "Net-(C18-1)") (class "Default")
      (node (ref "C18") (pin "P$1") (pinfunction "1_P$1") (pintype "passive"))
      (node (ref "D3") (pin "C") (pinfunction "C_C") (pintype "passive"))
      (node (ref "R10") (pin "1") (pinfunction "1_1") (pintype "passive"))
      (node (ref "RL2") (pin "1") (pinfunction "1_1") (pintype "power_in"))
    )
    (net (code "32") (name "Net-(C19-2)") (class "Default")
      (node (ref "C19") (pin "P$2") (pinfunction "2_P$2") (pintype "passive"))
      (node (ref "R18") (pin "2") (pinfunction "2_2") (pintype "passive"))
      (node (ref "VHF") (pin "1") (pinfunction "P_1") (pintype "passive"))
    )
    (net (code "33") (name "Net-(C23-2)") (class "Default")
      (node (ref "C23") (pin "P$2") (pinfunction "2_P$2") (pintype "passive"))
      (node (ref "Q3") (pin "4") (pinfunction "ADJ-BYP_4") (pintype "input"))
    )
    (net (code "34") (name "Net-(C26-1)") (class "Default")
      (node (ref "C26") (pin "P$1") (pinfunction "1_P$1") (pintype "passive"))
      (node (ref "C27") (pin "P$1") (pinfunction "1_P$1") (pintype "passive"))
      (node (ref "C38") (pin "P$2") (pinfunction "2_P$2") (pintype "passive"))
      (node (ref "L4") (pin "P$2") (pinfunction "2_P$2") (pintype "passive"))
    )
    (net (code "35") (name "Net-(C26-2)") (class "Default")
      (node (ref "C26") (pin "P$2") (pinfunction "2_P$2") (pintype "passive"))
      (node (ref "X1A") (pin "P$3") (pinfunction "1_P$3") (pintype "passive"))
    )
    (net (code "36") (name "Net-(C28-1)") (class "Default")
      (node (ref "C28") (pin "P$1") (pinfunction "1_P$1") (pintype "passive"))
      (node (ref "C38") (pin "P$1") (pinfunction "1_P$1") (pintype "passive"))
      (node (ref "C39") (pin "P$2") (pinfunction "2_P$2") (pintype "passive"))
      (node (ref "L5") (pin "P$2") (pinfunction "2_P$2") (pintype "passive"))
    )
    (net (code "37") (name "Net-(C29-1)") (class "Default")
      (node (ref "C29") (pin "P$1") (pinfunction "1_P$1") (pintype "passive"))
      (node (ref "C30") (pin "P$1") (pinfunction "1_P$1") (pintype "passive"))
      (node (ref "C39") (pin "P$1") (pinfunction "1_P$1") (pintype "passive"))
      (node (ref "L12") (pin "P$1") (pinfunction "1_P$1") (pintype "passive"))
    )
    (net (code "38") (name "Net-(C30-2)") (class "Default")
      (node (ref "C30") (pin "P$2") (pinfunction "2_P$2") (pintype "passive"))
      (node (ref "X1B") (pin "P$3") (pinfunction "1_P$3") (pintype "passive"))
    )
    (net (code "39") (name "Net-(C31-2)") (class "Default")
      (node (ref "C31") (pin "P$2") (pinfunction "2_P$2") (pintype "passive"))
      (node (ref "L15") (pin "P$2") (pinfunction "2_P$2") (pintype "passive"))
      (node (ref "L16") (pin "P$1") (pinfunction "1_P$1") (pintype "passive"))
      (node (ref "L18") (pin "P$1") (pinfunction "1_P$1") (pintype "passive"))
    )
    (net (code "40") (name "Net-(C32-2)") (class "Default")
      (node (ref "C32") (pin "P$2") (pinfunction "2_P$2") (pintype "passive"))
      (node (ref "L13") (pin "P$2") (pinfunction "2_P$2") (pintype "passive"))
      (node (ref "L14") (pin "P$1") (pinfunction "1_P$1") (pintype "passive"))
      (node (ref "L17") (pin "P$1") (pinfunction "1_P$1") (pintype "passive"))
    )
    (net (code "41") (name "Net-(C33-1)") (class "Default")
      (node (ref "C33") (pin "P$1") (pinfunction "1_P$1") (pintype "passive"))
      (node (ref "SW_BPF-IN") (pin "3") (pinfunction "NC_3") (pintype "bidirectional"))
    )
    (net (code "42") (name "Net-(C33-2)") (class "Default")
      (node (ref "C33") (pin "P$2") (pinfunction "2_P$2") (pintype "passive"))
      (node (ref "C47") (pin "P$1") (pinfunction "1_P$1") (pintype "passive"))
      (node (ref "C6") (pin "P$2") (pinfunction "2_P$2") (pintype "passive"))
      (node (ref "L10") (pin "P$1") (pinfunction "1_P$1") (pintype "passive"))
    )
    (net (code "43") (name "Net-(C35-1)") (class "Default")
      (node (ref "C35") (pin "P$1") (pinfunction "1_P$1") (pintype "passive"))
      (node (ref "C47") (pin "P$2") (pinfunction "2_P$2") (pintype "passive"))
      (node (ref "C7") (pin "P$2") (pinfunction "2_P$2") (pintype "passive"))
      (node (ref "L11") (pin "P$1") (pinfunction "1_P$1") (pintype "passive"))
    )
    (net (code "44") (name "Net-(C35-2)") (class "Default")
      (node (ref "C35") (pin "P$2") (pinfunction "2_P$2") (pintype "passive"))
      (node (ref "SW_BPF-OUT") (pin "3") (pinfunction "NC_3") (pintype "bidirectional"))
    )
    (net (code "45") (name "Net-(C37-1)") (class "Default")
      (node (ref "C37") (pin "P$1") (pinfunction "1_P$1") (pintype "passive"))
      (node (ref "C4") (pin "P$1") (pinfunction "1_P$1") (pintype "passive"))
      (node (ref "C5") (pin "P$1") (pinfunction "1_P$1") (pintype "passive"))
      (node (ref "L3") (pin "P$1") (pinfunction "1_P$1") (pintype "passive"))
    )
    (net (code "46") (name "Net-(C40-1)") (class "Default")
      (node (ref "C40") (pin "P$1") (pinfunction "1_P$1") (pintype "passive"))
      (node (ref "X3A") (pin "3") (pinfunction "SIGNAL_3") (pintype "passive"))
    )
    (net (code "47") (name "Net-(C40-2)") (class "Default")
      (node (ref "C40") (pin "P$2") (pinfunction "2_P$2") (pintype "passive"))
      (node (ref "C41") (pin "P$1") (pinfunction "1_P$1") (pintype "passive"))
      (node (ref "C42") (pin "P$1") (pinfunction "1_P$1") (pintype "passive"))
      (node (ref "L6") (pin "P$1") (pinfunction "1_P$1") (pintype "passive"))
    )
    (net (code "48") (name "Net-(C42-2)") (class "Default")
      (node (ref "C42") (pin "P$2") (pinfunction "2_P$2") (pintype "passive"))
      (node (ref "C43") (pin "P$1") (pinfunction "1_P$1") (pintype "passive"))
      (node (ref "C44") (pin "P$1") (pinfunction "1_P$1") (pintype "passive"))
      (node (ref "L8") (pin "P$1") (pinfunction "1_P$1") (pintype "passive"))
    )
    (net (code "49") (name "Net-(C44-2)") (class "Default")
      (node (ref "C44") (pin "P$2") (pinfunction "2_P$2") (pintype "passive"))
      (node (ref "C45") (pin "P$1") (pinfunction "1_P$1") (pintype "passive"))
      (node (ref "C46") (pin "P$2") (pinfunction "2_P$2") (pintype "passive"))
      (node (ref "L9") (pin "P$1") (pinfunction "1_P$1") (pintype "passive"))
    )
    (net (code "50") (name "Net-(C46-1)") (class "Default")
      (node (ref "C46") (pin "P$1") (pinfunction "1_P$1") (pintype "passive"))
      (node (ref "X3B") (pin "3") (pinfunction "SIGNAL_3") (pintype "passive"))
    )
    (net (code "51") (name "Net-(FB1-1)") (class "Default")
      (node (ref "F1") (pin "1") (pinfunction "1_1") (pintype "passive"))
      (node (ref "FB1") (pin "P$1") (pinfunction "1_P$1") (pintype "passive"))
    )
    (net (code "52") (name "Net-(FB2-1)") (class "Default")
      (node (ref "FB2") (pin "P$1") (pinfunction "1_P$1") (pintype "passive"))
      (node (ref "R5") (pin "1") (pinfunction "1_1") (pintype "passive"))
    )
    (net (code "53") (name "Net-(FB3-1)") (class "Default")
      (node (ref "FB3") (pin "P$1") (pinfunction "1_P$1") (pintype "passive"))
      (node (ref "R6") (pin "1") (pinfunction "1_1") (pintype "passive"))
    )
    (net (code "54") (name "Net-(FB4-1)") (class "Default")
      (node (ref "FB4") (pin "P$1") (pinfunction "1_P$1") (pintype "passive"))
      (node (ref "R7") (pin "1") (pinfunction "1_1") (pintype "passive"))
    )
    (net (code "55") (name "Net-(FB5-1)") (class "Default")
      (node (ref "FB5") (pin "P$1") (pinfunction "1_P$1") (pintype "passive"))
      (node (ref "R18") (pin "1") (pinfunction "1_1") (pintype "passive"))
    )
    (net (code "56") (name "Net-(FB6-1)") (class "Default")
      (node (ref "FB6") (pin "P$1") (pinfunction "1_P$1") (pintype "passive"))
      (node (ref "R12") (pin "1") (pinfunction "1_1") (pintype "passive"))
    )
    (net (code "57") (name "Net-(L7-1)") (class "Default")
      (node (ref "L7") (pin "P$1") (pinfunction "1_P$1") (pintype "passive"))
      (node (ref "R8") (pin "1") (pinfunction "1_1") (pintype "passive"))
    )
    (net (code "58") (name "Net-(L13-1)") (class "Default")
      (node (ref "L13") (pin "P$1") (pinfunction "1_P$1") (pintype "passive"))
      (node (ref "L18") (pin "P$2") (pinfunction "2_P$2") (pintype "passive"))
    )
    (net (code "59") (name "Net-(L14-2)") (class "Default")
      (node (ref "L14") (pin "P$2") (pinfunction "2_P$2") (pintype "passive"))
      (node (ref "X2B") (pin "3") (pinfunction "SIGNAL_3") (pintype "passive"))
    )
    (net (code "60") (name "Net-(L15-1)") (class "Default")
      (node (ref "L15") (pin "P$1") (pinfunction "1_P$1") (pintype "passive"))
      (node (ref "X2A") (pin "3") (pinfunction "SIGNAL_3") (pintype "passive"))
    )
    (net (code "61") (name "Net-(Q2-4)") (class "Default")
      (node (ref "Q2") (pin "5") (pinfunction "5_5") (pintype "input"))
      (node (ref "Q2") (pin "6") (pinfunction "4_6") (pintype "passive"))
    )
    (net (code "62") (name "Net-(R11-Pad2)") (class "Default")
      (node (ref "R11") (pin "2") (pinfunction "2_2") (pintype "passive"))
      (node (ref "R16") (pin "2") (pinfunction "2_2") (pintype "passive"))
      (node (ref "X8") (pin "1") (pinfunction "GND_1") (pintype "passive"))
      (node (ref "X8") (pin "2") (pinfunction "GND_2") (pintype "passive"))
    )
    (net (code "63") (name "Net-(X7-SIGNAL)") (class "Default")
      (node (ref "X7") (pin "1") (pinfunction "GND_1") (pintype "passive"))
      (node (ref "X7") (pin "2") (pinfunction "GND_2") (pintype "passive"))
      (node (ref "X7") (pin "3") (pinfunction "SIGNAL_3") (pintype "passive"))
    )
    (net (code "64") (name "Net-(X8-SIGNAL)") (class "Default")
      (node (ref "R11") (pin "1") (pinfunction "1_1") (pintype "passive"))
      (node (ref "R16") (pin "1") (pinfunction "1_1") (pintype "passive"))
      (node (ref "X8") (pin "3") (pinfunction "SIGNAL_3") (pintype "passive"))
    )
    (net (code "65") (name "Net-(X10-SIGNAL)") (class "Default")
      (node (ref "X10") (pin "3") (pinfunction "SIGNAL_3") (pintype "passive"))
      (node (ref "X9") (pin "3") (pinfunction "SIGNAL_3") (pintype "passive"))
    )
    (net (code "66") (name "RADIO") (class "Default")
      (node (ref "RL2") (pin "6") (pinfunction "6_6") (pintype "bidirectional"))
      (node (ref "X2") (pin "1") (pinfunction "1_1") (pintype "passive"))
    )
    (net (code "67") (name "RADIO_TX") (class "Default")
      (node (ref "Q1") (pin "1") (pinfunction "A_1") (pintype "input"))
      (node (ref "R13") (pin "1") (pinfunction "1_1") (pintype "passive"))
      (node (ref "T1") (pin "C") (pinfunction "C_C") (pintype "passive"))
      (node (ref "TP-RADIO-TX") (pin "TP") (pinfunction "TP_TP") (pintype "input"))
    )
    (net (code "68") (name "RELAY-RX_ON") (class "Default")
      (node (ref "FB2") (pin "P$2") (pinfunction "2_P$2") (pintype "passive"))
      (node (ref "Q2") (pin "3") (pinfunction "3_3") (pintype "passive"))
      (node (ref "R10") (pin "2") (pinfunction "2_2") (pintype "passive"))
      (node (ref "R9") (pin "1") (pinfunction "1_1") (pintype "passive"))
      (node (ref "TP-RLY-ON") (pin "TP") (pinfunction "TP_TP") (pintype "input"))
    )
    (net (code "69") (name "RELAY-TO-RELAY_RF") (class "Default")
      (node (ref "RL1") (pin "20") (pinfunction "20_20") (pintype "bidirectional"))
      (node (ref "RL2") (pin "20") (pinfunction "20_20") (pintype "bidirectional"))
    )
    (net (code "70") (name "SEL_BPF_VHF") (class "Default")
      (node (ref "FB5") (pin "P$2") (pinfunction "2_P$2") (pintype "passive"))
      (node (ref "R17") (pin "1") (pinfunction "1_1") (pintype "passive"))
      (node (ref "SW_BPF-IN") (pin "4") (pinfunction "CTRL_4") (pintype "input"))
      (node (ref "SW_BPF-OUT") (pin "4") (pinfunction "CTRL_4") (pintype "input"))
      (node (ref "TP-VHF-ON") (pin "TP") (pinfunction "TP_TP") (pintype "input"))
    )
    (net (code "71") (name "TO_BPF") (class "Default")
      (node (ref "C25") (pin "P$2") (pinfunction "2_P$2") (pintype "passive"))
      (node (ref "D1") (pin "2") (pinfunction "C_2") (pintype "passive"))
      (node (ref "R8") (pin "2") (pinfunction "2_2") (pintype "passive"))
      (node (ref "RL1") (pin "14") (pinfunction "14_14") (pintype "bidirectional"))
    )
    (net (code "72") (name "unconnected-(Q6-NC-Pad4)") (class "Default")
      (node (ref "Q6") (pin "4") (pinfunction "NC_4") (pintype "no_connect"))
    )
    (net (code "73") (name "unconnected-(X6-GND-Pad1)") (class "Default")
      (node (ref "X6") (pin "1") (pinfunction "GND_1") (pintype "passive"))
    )
    (net (code "74") (name "unconnected-(X6-GND-Pad2)") (class "Default")
      (node (ref "X6") (pin "2") (pinfunction "GND_2") (pintype "passive"))
    )
    (net (code "75") (name "unconnected-(X6-SIGNAL-Pad3)") (class "Default")
      (node (ref "X6") (pin "3") (pinfunction "SIGNAL_3") (pintype "passive"))
    )
  )
)
